# easyeda-schematic.net
KiCad netlist of a schematic drawn in EasyEDA
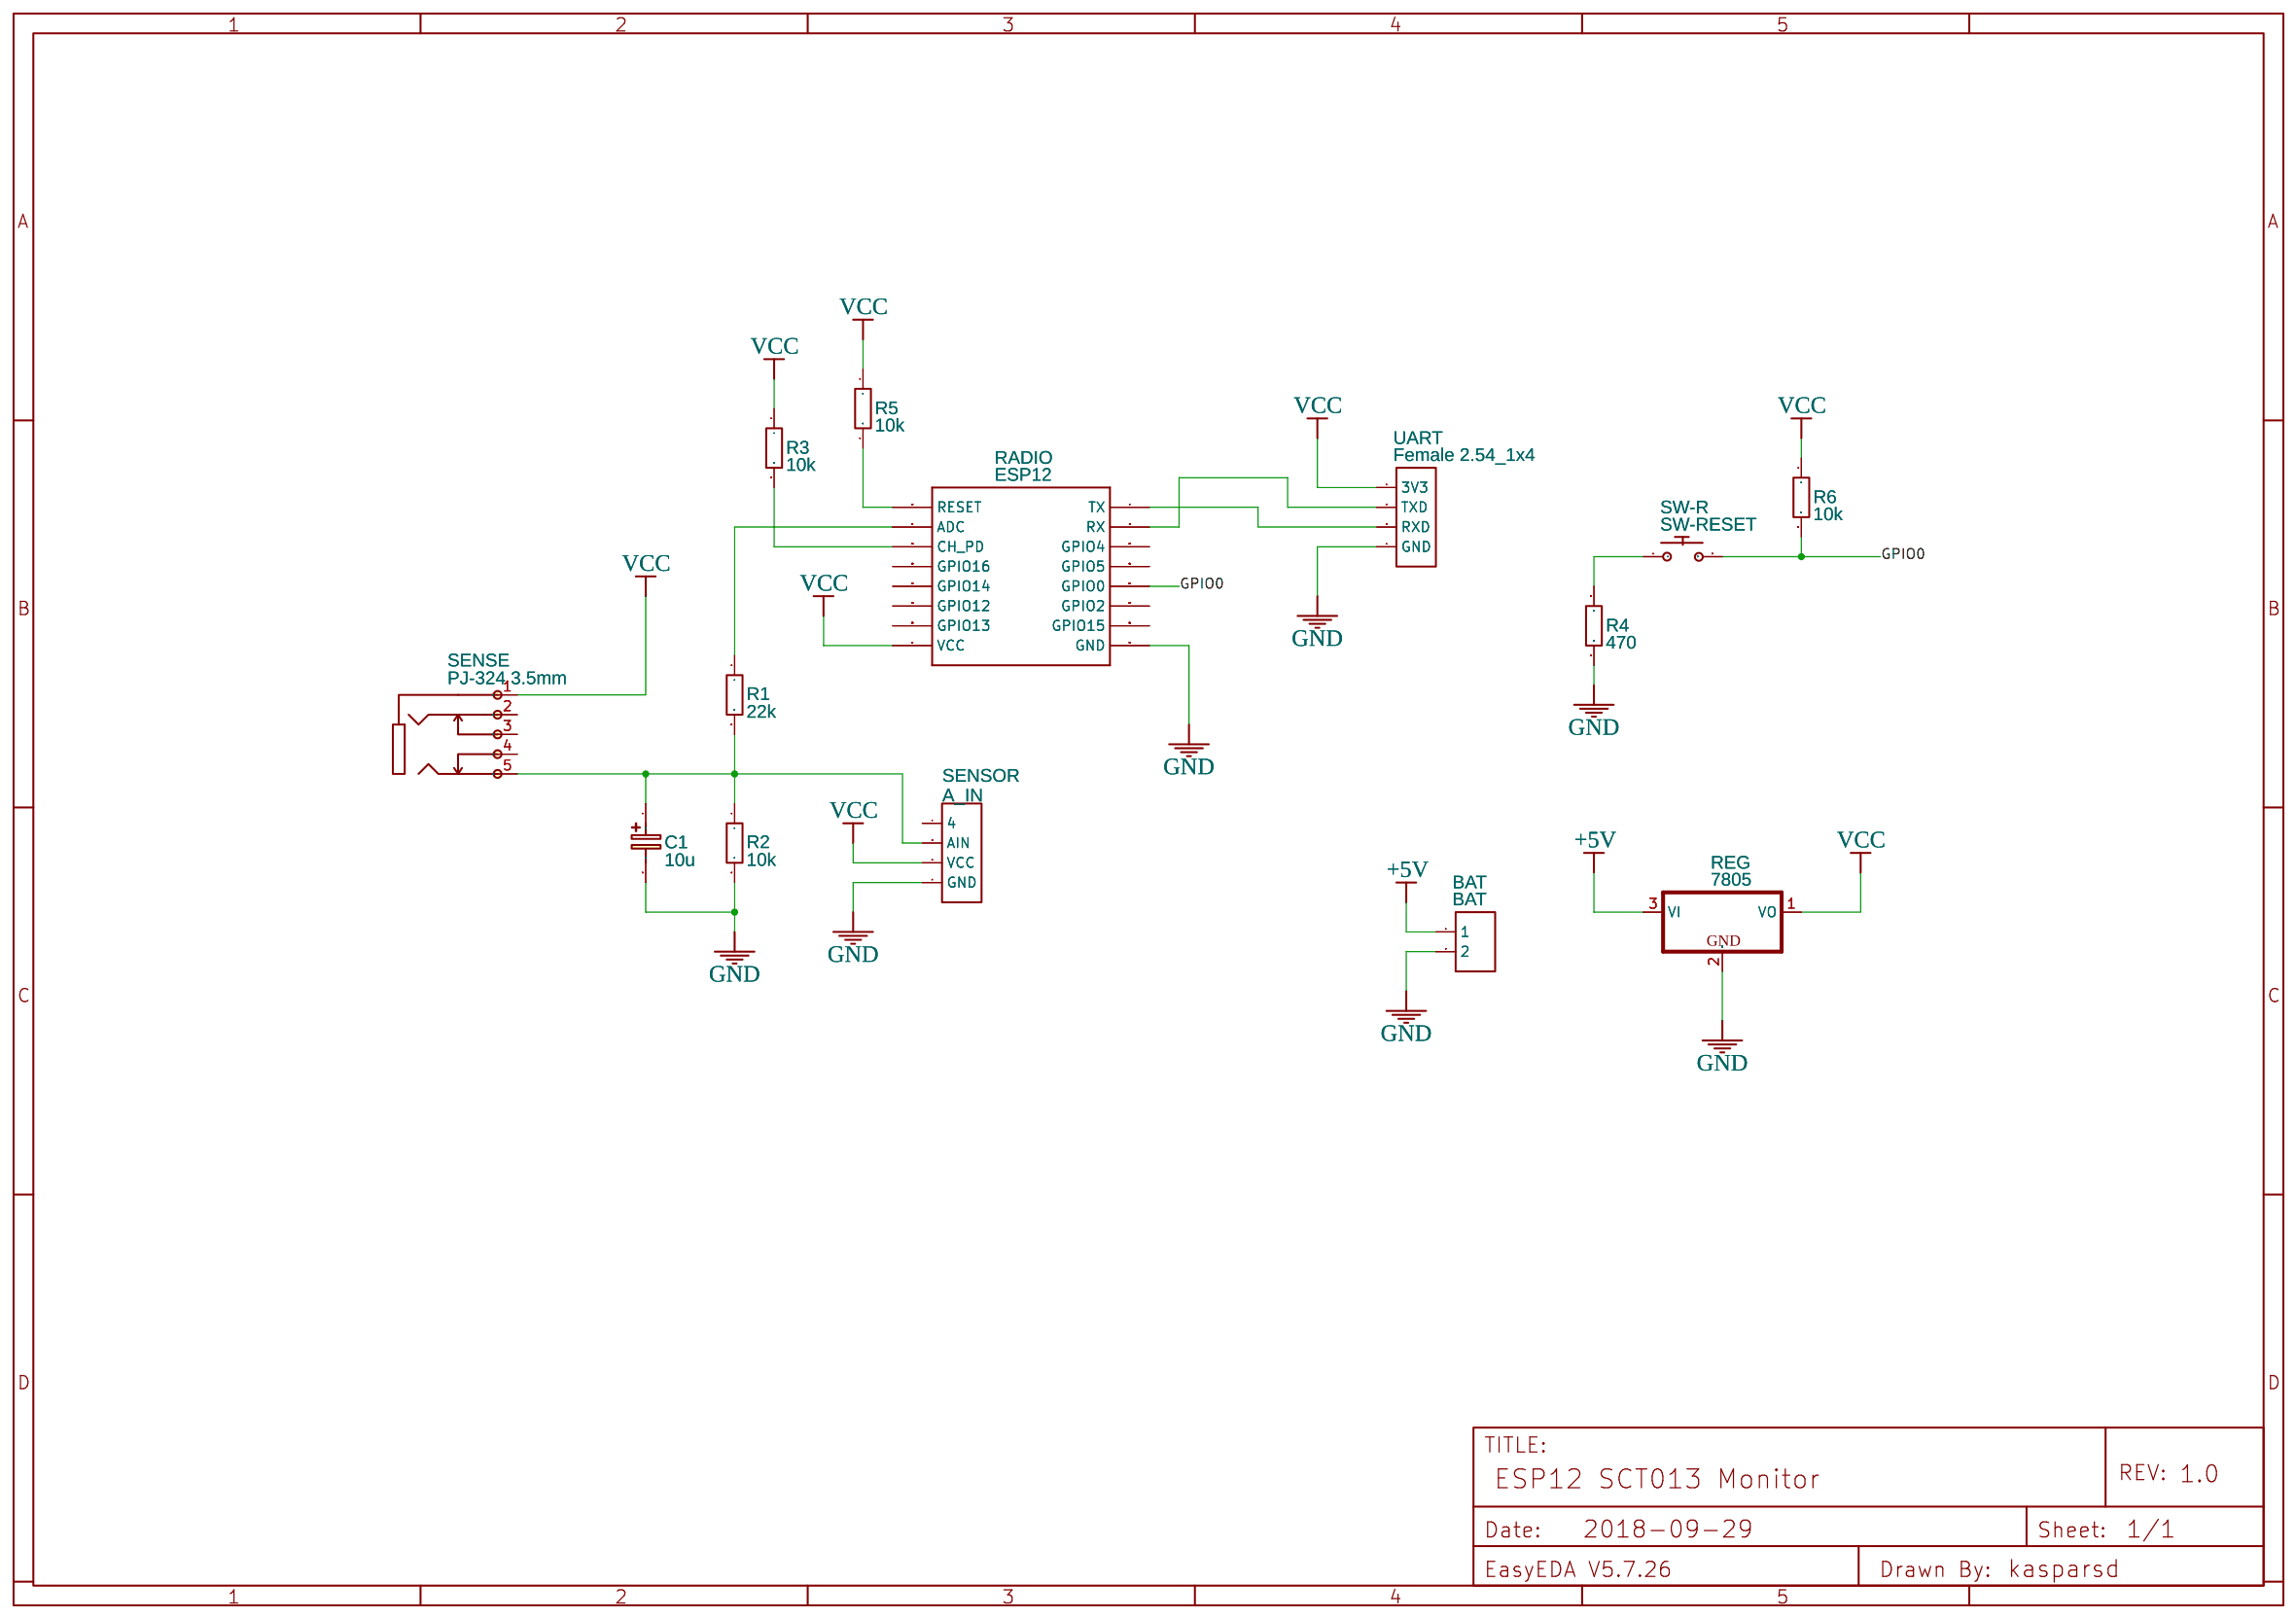
[diagram p0: schematic sheet]

(export (version "E")
  (design (tool "Eeschema 10.0.6"))
  (components
    (comp (ref "BAT")
      (value "BAT")
      (fields
        (field (name "BOM_Manufacturer Part") "2.54-1*2PFemale")
        (field (name "BOM_Supplier Part") "C49661")
      )
      (libsource (lib "") (part "Unknown_735_470"))
    )
    (comp (ref "C1")
      (value "10u")
      (fields (field (name "BOM_Manufacturer Part") "?"))
      (libsource (lib "") (part "Cap_Electrolytic(TH)_D5.0XF2.0_EU"))
    )
    (comp (ref "R1")
      (value "22k")
      (fields (field (name "BOM_Manufacturer Part") "?"))
      (libsource (lib "") (part "Res_AXIAL-0.3(1/8W)_EU"))
    )
    (comp (ref "R2")
      (value "10k")
      (fields (field (name "BOM_Manufacturer Part") "?"))
      (libsource (lib "") (part "Res_AXIAL-0.3(1/8W)_EU"))
    )
    (comp (ref "R3")
      (value "10k")
      (fields (field (name "BOM_Manufacturer Part") "?"))
      (libsource (lib "") (part "Res_AXIAL-0.3(1/8W)_EU"))
    )
    (comp (ref "R4")
      (value "470")
      (fields (field (name "BOM_Manufacturer Part") "?"))
      (libsource (lib "") (part "Res_AXIAL-0.3(1/8W)_EU"))
    )
    (comp (ref "R5")
      (value "10k")
      (fields (field (name "BOM_Manufacturer Part") "?"))
      (libsource (lib "") (part "Res_AXIAL-0.3(1/8W)_EU"))
    )
    (comp (ref "R6")
      (value "10k")
      (fields (field (name "BOM_Manufacturer Part") "?"))
      (libsource (lib "") (part "Res_AXIAL-0.3(1/8W)_EU"))
    )
    (comp (ref "RADIO")
      (value "ESP12")
      (fields (field (name "BOM_Manufacturer Part") "?"))
      (libsource (lib "") (part "Unknown_510_275"))
    )
    (comp (ref "REG")
      (value "7805")
      (fields (field (name "BOM_Manufacturer Part") "?"))
      (libsource (lib "") (part "Unknown_865_455"))
    )
    (comp (ref "SENSE")
      (value "PJ-324 3.5mm")
      (fields
        (field (name "BOM_Manufacturer Part") "PJ-324 3.5mmAudio sockets")
        (field (name "BOM_Supplier Part") "C34345")
      )
      (libsource (lib "") (part "Unknown_255_365"))
    )
    (comp (ref "SENSOR")
      (value "A_IN")
      (fields
        (field (name "BOM_Manufacturer Part") "Header-Female-2.54_1x4")
        (field (name "BOM_Supplier Part") "C124413")
      )
      (libsource (lib "") (part "Unknown_475_425"))
    )
    (comp (ref "SW-R")
      (value "SW-RESET")
      (fields (field (name "BOM_Manufacturer Part") "?"))
      (libsource (lib "") (part "Unknown_845_275"))
    )
    (comp (ref "UART")
      (value "Female 2.54_1x4")
      (fields
        (field (name "BOM_Manufacturer Part") "Header-Female-2.54_1x4")
        (field (name "BOM_Supplier Part") "C124413")
      )
      (libsource (lib "") (part "Unknown_705_255"))
    )
  )
  (nets
    (net (code "1") (name "+5V") (class "Default")
      (node (ref "BAT") (pin "1") (pinfunction "1_1") (pintype "input"))
      (node (ref "REG") (pin "3") (pinfunction "VI_3") (pintype "input"))
    )
    (net (code "2") (name "/GPIO0") (class "Default")
      (node (ref "R6") (pin "2") (pinfunction "2_2") (pintype "unspecified"))
      (node (ref "RADIO") (pin "GPIO0") (pinfunction "GPIO0_GPIO0") (pintype "unspecified"))
      (node (ref "SW-R") (pin "2") (pinfunction "2_2") (pintype "unspecified"))
    )
    (net (code "3") (name "GND") (class "Default")
      (node (ref "BAT") (pin "2") (pinfunction "2_2") (pintype "input"))
      (node (ref "C1") (pin "2") (pinfunction "2_2") (pintype "unspecified"))
      (node (ref "R2") (pin "2") (pinfunction "2_2") (pintype "unspecified"))
      (node (ref "R4") (pin "2") (pinfunction "2_2") (pintype "unspecified"))
      (node (ref "RADIO") (pin "GND") (pinfunction "GND_GND") (pintype "unspecified"))
      (node (ref "REG") (pin "2") (pinfunction "GND_2") (pintype "unspecified"))
      (node (ref "SENSOR") (pin "1") (pinfunction "GND_1") (pintype "input"))
      (node (ref "UART") (pin "4") (pinfunction "GND_4") (pintype "input"))
    )
    (net (code "4") (name "Net-(R1-Pad1)") (class "Default")
      (node (ref "R1") (pin "1") (pinfunction "1_1") (pintype "unspecified"))
      (node (ref "RADIO") (pin "ADC") (pinfunction "ADC_ADC") (pintype "unspecified"))
    )
    (net (code "5") (name "Net-(R3-Pad2)") (class "Default")
      (node (ref "R3") (pin "2") (pinfunction "2_2") (pintype "unspecified"))
      (node (ref "RADIO") (pin "CH_PD") (pinfunction "CH_PD_CH_PD") (pintype "unspecified"))
    )
    (net (code "6") (name "Net-(R4-Pad1)") (class "Default")
      (node (ref "R4") (pin "1") (pinfunction "1_1") (pintype "unspecified"))
      (node (ref "SW-R") (pin "1") (pinfunction "1_1") (pintype "unspecified"))
    )
    (net (code "7") (name "Net-(R5-Pad2)") (class "Default")
      (node (ref "R5") (pin "2") (pinfunction "2_2") (pintype "unspecified"))
      (node (ref "RADIO") (pin "RESET") (pinfunction "RESET_RESET") (pintype "unspecified"))
    )
    (net (code "8") (name "Net-(SENSOR-AIN)") (class "Default")
      (node (ref "C1") (pin "1") (pinfunction "1_1") (pintype "unspecified"))
      (node (ref "R1") (pin "2") (pinfunction "2_2") (pintype "unspecified"))
      (node (ref "R2") (pin "1") (pinfunction "1_1") (pintype "unspecified"))
      (node (ref "SENSE") (pin "5") (pinfunction "5_5") (pintype "input"))
      (node (ref "SENSOR") (pin "3") (pinfunction "AIN_3") (pintype "input"))
    )
    (net (code "9") (name "Net-(UART-RXD)") (class "Default")
      (node (ref "RADIO") (pin "TX") (pinfunction "TX_TX") (pintype "unspecified"))
      (node (ref "UART") (pin "3") (pinfunction "RXD_3") (pintype "input"))
    )
    (net (code "10") (name "Net-(UART-TXD)") (class "Default")
      (node (ref "RADIO") (pin "RX") (pinfunction "RX_RX") (pintype "unspecified"))
      (node (ref "UART") (pin "2") (pinfunction "TXD_2") (pintype "input"))
    )
    (net (code "11") (name "VCC") (class "Default")
      (node (ref "R3") (pin "1") (pinfunction "1_1") (pintype "unspecified"))
      (node (ref "R5") (pin "1") (pinfunction "1_1") (pintype "unspecified"))
      (node (ref "R6") (pin "1") (pinfunction "1_1") (pintype "unspecified"))
      (node (ref "RADIO") (pin "VCC") (pinfunction "VCC_VCC") (pintype "unspecified"))
      (node (ref "REG") (pin "1") (pinfunction "VO_1") (pintype "unspecified"))
      (node (ref "SENSE") (pin "1") (pinfunction "1_1") (pintype "input"))
      (node (ref "SENSOR") (pin "2") (pinfunction "VCC_2") (pintype "input"))
      (node (ref "UART") (pin "1") (pinfunction "3V3_1") (pintype "input"))
    )
    (net (code "12") (name "unconnected-(RADIO-PadGPIO2)") (class "Default")
      (node (ref "RADIO") (pin "GPIO2") (pinfunction "GPIO2_GPIO2") (pintype "unspecified"))
    )
    (net (code "13") (name "unconnected-(RADIO-PadGPIO4)") (class "Default")
      (node (ref "RADIO") (pin "GPIO4") (pinfunction "GPIO4_GPIO4") (pintype "unspecified"))
    )
    (net (code "14") (name "unconnected-(RADIO-PadGPIO5)") (class "Default")
      (node (ref "RADIO") (pin "GPIO5") (pinfunction "GPIO5_GPIO5") (pintype "unspecified"))
    )
    (net (code "15") (name "unconnected-(RADIO-PadGPIO12)") (class "Default")
      (node (ref "RADIO") (pin "GPIO12") (pinfunction "GPIO12_GPIO12") (pintype "unspecified"))
    )
    (net (code "16") (name "unconnected-(RADIO-PadGPIO13)") (class "Default")
      (node (ref "RADIO") (pin "GPIO13") (pinfunction "GPIO13_GPIO13") (pintype "unspecified"))
    )
    (net (code "17") (name "unconnected-(RADIO-PadGPIO14)") (class "Default")
      (node (ref "RADIO") (pin "GPIO14") (pinfunction "GPIO14_GPIO14") (pintype "unspecified"))
    )
    (net (code "18") (name "unconnected-(RADIO-PadGPIO15)") (class "Default")
      (node (ref "RADIO") (pin "GPIO15") (pinfunction "GPIO15_GPIO15") (pintype "unspecified"))
    )
    (net (code "19") (name "unconnected-(RADIO-PadGPIO16)") (class "Default")
      (node (ref "RADIO") (pin "GPIO16") (pinfunction "GPIO16_GPIO16") (pintype "unspecified"))
    )
    (net (code "20") (name "unconnected-(SENSE-Pad2)") (class "Default")
      (node (ref "SENSE") (pin "2") (pinfunction "2_2") (pintype "input"))
    )
    (net (code "21") (name "unconnected-(SENSE-Pad3)") (class "Default")
      (node (ref "SENSE") (pin "3") (pinfunction "3_3") (pintype "input"))
    )
    (net (code "22") (name "unconnected-(SENSE-Pad4)") (class "Default")
      (node (ref "SENSE") (pin "4") (pinfunction "4_4") (pintype "input"))
    )
    (net (code "23") (name "unconnected-(SENSOR-Pad4)") (class "Default")
      (node (ref "SENSOR") (pin "4") (pinfunction "4_4") (pintype "input"))
    )
  )
)
